# Input_channel.net
KiCad netlist of a schematic drawn in Altium Designer
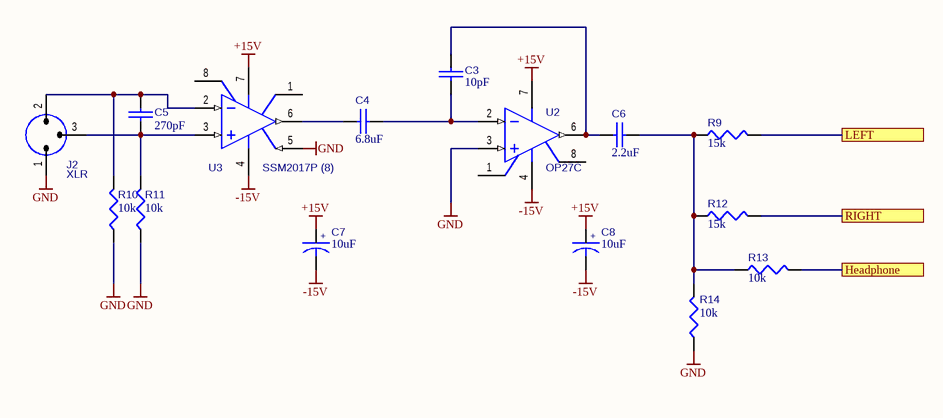
[diagram p0:  Input channel.SchDoc]

(export (version "E")
  (design (tool "Eeschema 10.0.6"))
  (components
    (comp (ref "C3")
      (value "10pF")
      (footprint "RAD0.2")
      (description "Capacitor")
      (libsource (lib "*") (part "CAP"))
    )
    (comp (ref "C4")
      (value "6.8uF")
      (footprint "RB.2/.4-NP")
      (description "Capacitor")
      (libsource (lib "*") (part "CAP"))
    )
    (comp (ref "C5")
      (value "270pF")
      (footprint "RAD0.2")
      (description "Capacitor")
      (libsource (lib "*") (part "CAP"))
    )
    (comp (ref "C6")
      (value "2.2uF")
      (footprint "RB.2/.4-NP")
      (description "Capacitor")
      (libsource (lib "*") (part "CAP"))
    )
    (comp (ref "C7")
      (value "10uF")
      (footprint "RB.2/.4")
      (description "Bi-Polar Capacitor")
      (libsource (lib "*") (part "CAPACITOR POL"))
    )
    (comp (ref "C8")
      (value "10uF")
      (footprint "RB.2/.4")
      (description "Bi-Polar Capacitor")
      (libsource (lib "*") (part "CAPACITOR POL"))
    )
    (comp (ref "J2")
      (value "XLR")
      (footprint "XLR-FEMALE")
      (description "XLR connector, PCB mounted")
      (libsource (lib "*") (part "XLR"))
    )
    (comp (ref "R9")
      (value "15k")
      (footprint "AXIAL0.4")
      (description "Resistor")
      (libsource (lib "*") (part "RES1"))
    )
    (comp (ref "R10")
      (value "10k")
      (footprint "AXIAL0.4")
      (description "Resistor")
      (libsource (lib "") (part "RES1_1"))
    )
    (comp (ref "R11")
      (value "10k")
      (footprint "AXIAL0.4")
      (description "Resistor")
      (libsource (lib "") (part "RES1_1"))
    )
    (comp (ref "R12")
      (value "15k")
      (footprint "AXIAL0.4")
      (description "Resistor")
      (libsource (lib "*") (part "RES1"))
    )
    (comp (ref "R13")
      (value "10k")
      (footprint "AXIAL0.4")
      (description "Resistor")
      (libsource (lib "*") (part "RES1"))
    )
    (comp (ref "R14")
      (value "10k")
      (footprint "AXIAL0.4")
      (description "Resistor")
      (libsource (lib "") (part "RES1_1"))
    )
    (comp (ref "U2")
      (value "OP27C")
      (footprint "DIP8")
      (description "Low Noise, High Speed Precision Operational Amplifier")
      (libsource (lib "*") (part "OP27C"))
    )
    (comp (ref "U3")
      (value "SSM2017P (8)")
      (footprint "DIP8")
      (description "Self-Contained Audio Preamplifier")
      (libsource (lib "*") (part "SSM2017P (8)"))
    )
  )
  (nets
    (net (code "1") (name "+15V") (class "Default")
      (node (ref "C7") (pin "1") (pinfunction "1_1") (pintype "passive"))
      (node (ref "C8") (pin "1") (pinfunction "1_1") (pintype "passive"))
      (node (ref "U2") (pin "7") (pinfunction "V+_7") (pintype "power_in"))
      (node (ref "U3") (pin "7") (pinfunction "V+_7") (pintype "power_in"))
    )
    (net (code "2") (name "-15V") (class "Default")
      (node (ref "C7") (pin "2") (pinfunction "2_2") (pintype "passive"))
      (node (ref "C8") (pin "2") (pinfunction "2_2") (pintype "passive"))
      (node (ref "U2") (pin "4") (pinfunction "V-_4") (pintype "power_in"))
      (node (ref "U3") (pin "4") (pinfunction "V-_4") (pintype "power_in"))
    )
    (net (code "3") (name "/Headphone") (class "Default")
      (node (ref "R13") (pin "2") (pinfunction "2_2") (pintype "passive"))
    )
    (net (code "4") (name "/LEFT") (class "Default")
      (node (ref "R9") (pin "2") (pinfunction "2_2") (pintype "passive"))
    )
    (net (code "5") (name "/RIGHT") (class "Default")
      (node (ref "R12") (pin "2") (pinfunction "2_2") (pintype "passive"))
    )
    (net (code "6") (name "GND") (class "Default")
      (node (ref "J2") (pin "1") (pinfunction "1_1") (pintype "passive"))
      (node (ref "R10") (pin "1") (pinfunction "1_1") (pintype "passive"))
      (node (ref "R11") (pin "1") (pinfunction "1_1") (pintype "passive"))
      (node (ref "R14") (pin "1") (pinfunction "1_1") (pintype "passive"))
      (node (ref "U2") (pin "3") (pinfunction "+IN_3") (pintype "input"))
      (node (ref "U3") (pin "5") (pinfunction "REF_5") (pintype "input"))
    )
    (net (code "7") (name "Net-(C6-Pad2)") (class "Default")
      (node (ref "C6") (pin "2") (pinfunction "2_2") (pintype "passive"))
      (node (ref "R12") (pin "1") (pinfunction "1_1") (pintype "passive"))
      (node (ref "R13") (pin "1") (pinfunction "1_1") (pintype "passive"))
      (node (ref "R14") (pin "2") (pinfunction "2_2") (pintype "passive"))
      (node (ref "R9") (pin "1") (pinfunction "1_1") (pintype "passive"))
    )
    (net (code "8") (name "Net-(U2--IN)") (class "Default")
      (node (ref "C3") (pin "1") (pinfunction "1_1") (pintype "passive"))
      (node (ref "C4") (pin "2") (pinfunction "2_2") (pintype "passive"))
      (node (ref "U2") (pin "2") (pinfunction "-IN_2") (pintype "input"))
    )
    (net (code "9") (name "Net-(U2-OUT)") (class "Default")
      (node (ref "C3") (pin "2") (pinfunction "2_2") (pintype "passive"))
      (node (ref "C6") (pin "1") (pinfunction "1_1") (pintype "passive"))
      (node (ref "U2") (pin "6") (pinfunction "OUT_6") (pintype "output"))
    )
    (net (code "10") (name "Net-(U3-IN+)") (class "Default")
      (node (ref "C5") (pin "2") (pinfunction "2_2") (pintype "passive"))
      (node (ref "J2") (pin "3") (pinfunction "3_3") (pintype "passive"))
      (node (ref "R11") (pin "2") (pinfunction "2_2") (pintype "passive"))
      (node (ref "U3") (pin "3") (pinfunction "IN+_3") (pintype "input"))
    )
    (net (code "11") (name "Net-(U3-IN-)") (class "Default")
      (node (ref "C5") (pin "1") (pinfunction "1_1") (pintype "passive"))
      (node (ref "J2") (pin "2") (pinfunction "2_2") (pintype "passive"))
      (node (ref "R10") (pin "2") (pinfunction "2_2") (pintype "passive"))
      (node (ref "U3") (pin "2") (pinfunction "IN-_2") (pintype "input"))
    )
    (net (code "12") (name "Net-(U3-OUT)") (class "Default")
      (node (ref "C4") (pin "1") (pinfunction "1_1") (pintype "passive"))
      (node (ref "U3") (pin "6") (pinfunction "OUT_6") (pintype "output"))
    )
    (net (code "13") (name "unconnected-(U2-TRIM-Pad1)") (class "Default")
      (node (ref "U2") (pin "1") (pinfunction "TRIM_1") (pintype "passive"))
    )
    (net (code "14") (name "unconnected-(U2-TRIM-Pad8)") (class "Default")
      (node (ref "U2") (pin "8") (pinfunction "TRIM_8") (pintype "passive"))
    )
    (net (code "15") (name "unconnected-(U3-RG1-Pad1)") (class "Default")
      (node (ref "U3") (pin "1") (pinfunction "RG1_1") (pintype "passive"))
    )
    (net (code "16") (name "unconnected-(U3-RG2-Pad8)") (class "Default")
      (node (ref "U3") (pin "8") (pinfunction "RG2_8") (pintype "passive"))
    )
  )
)
